# Buck.net
KiCad netlist of a schematic drawn in Altium Designer
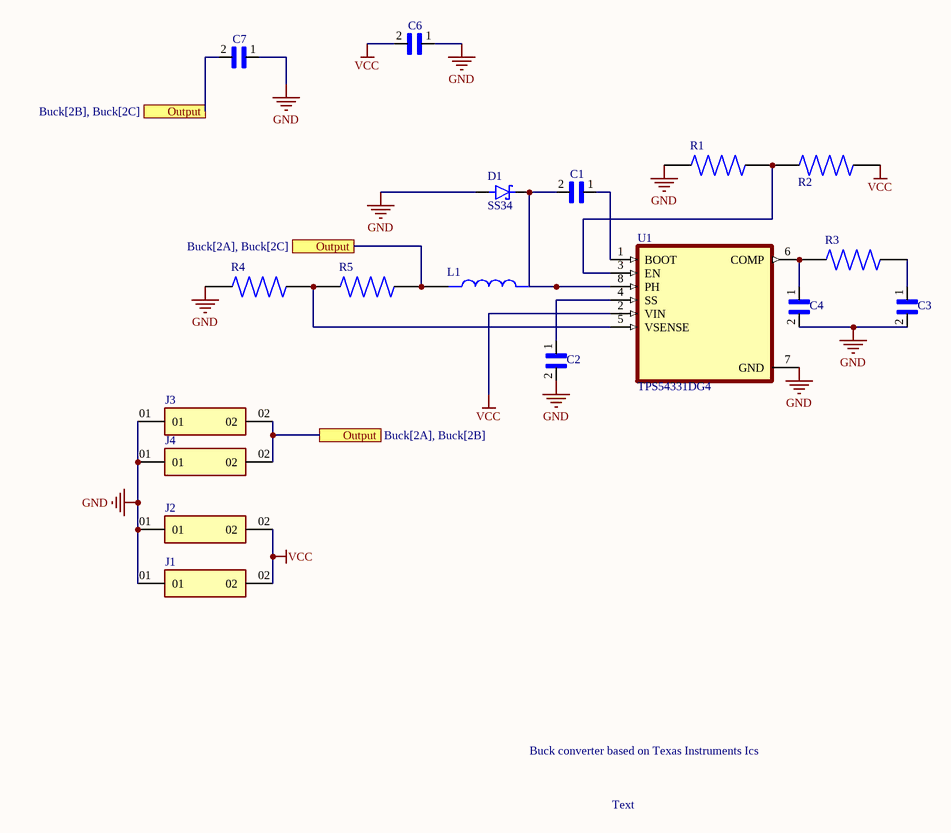
[diagram p0: Buck.SchDoc]

(export (version "E")
  (design (tool "Eeschema 10.0.6"))
  (components
    (comp (ref "C1")
      (value "~")
      (footprint "CAPC2012X135N")
      (description "SMD Capacitor X5R(EIA) with Capacitance: 22uF Tol. 20%. Rated Voltage: 25Vdc")
      (fields (field (name "MP") "GRM21BR61E226ME44K") (field (name "MF") "Murata Electronics"))
      (libsource (lib "GRM21BR61E226ME44K") (part "GRM21BR61E226ME44K"))
    )
    (comp (ref "C2")
      (value "~")
      (footprint "CAPC2012X135N")
      (description "SMD Capacitor X5R(EIA) with Capacitance: 22uF Tol. 20%. Rated Voltage: 25Vdc")
      (fields (field (name "MP") "GRM21BR61E226ME44K") (field (name "MF") "Murata Electronics"))
      (libsource (lib "") (part "GRM21BR61E226ME44K_1"))
    )
    (comp (ref "C3")
      (value "~")
      (footprint "CAPC2012X135N")
      (description "SMD Capacitor X5R(EIA) with Capacitance: 22uF Tol. 20%. Rated Voltage: 25Vdc")
      (fields (field (name "MP") "GRM21BR61E226ME44K") (field (name "MF") "Murata Electronics"))
      (libsource (lib "") (part "GRM21BR61E226ME44K_1"))
    )
    (comp (ref "C4")
      (value "~")
      (footprint "CAPC2012X135N")
      (description "SMD Capacitor X5R(EIA) with Capacitance: 22uF Tol. 20%. Rated Voltage: 25Vdc")
      (fields (field (name "MP") "GRM21BR61E226ME44K") (field (name "MF") "Murata Electronics"))
      (libsource (lib "") (part "GRM21BR61E226ME44K_1"))
    )
    (comp (ref "C6")
      (value "~")
      (footprint "CAPC2012X135N")
      (description "SMD Capacitor X5R(EIA) with Capacitance: 22uF Tol. 20%. Rated Voltage: 25Vdc")
      (fields (field (name "MP") "GRM21BR61E226ME44K") (field (name "MF") "Murata Electronics"))
      (libsource (lib "GRM21BR61E226ME44K") (part "GRM21BR61E226ME44K"))
    )
    (comp (ref "C7")
      (value "~")
      (footprint "CAPC2012X135N")
      (description "SMD Capacitor X5R(EIA) with Capacitance: 22uF Tol. 20%. Rated Voltage: 25Vdc")
      (fields (field (name "MP") "GRM21BR61E226ME44K") (field (name "MF") "Murata Electronics"))
      (libsource (lib "GRM21BR61E226ME44K") (part "GRM21BR61E226ME44K"))
    )
    (comp (ref "D1")
      (value "SS34")
      (footprint "DIO_SS34")
      (description "3A, 40V, Schottky Rectifier")
      (fields (field (name "MF") "Taiwan Semiconductor"))
      (libsource (lib "SS34") (part "SS34"))
    )
    (comp (ref "J1")
      (value "TSW-101-23-S-D-LL")
      (footprint "SAMTEC_TSW-101-23-S-D-LL")
      (libsource (lib "TSW-101-23-S-D-LL") (part "TSW-101-23-S-D-LL"))
    )
    (comp (ref "J2")
      (value "TSW-101-23-S-D-LL")
      (footprint "SAMTEC_TSW-101-23-S-D-LL")
      (libsource (lib "TSW-101-23-S-D-LL") (part "TSW-101-23-S-D-LL"))
    )
    (comp (ref "J3")
      (value "TSW-101-23-S-D-LL")
      (footprint "SAMTEC_TSW-101-23-S-D-LL")
      (libsource (lib "TSW-101-23-S-D-LL") (part "TSW-101-23-S-D-LL"))
    )
    (comp (ref "J4")
      (value "TSW-101-23-S-D-LL")
      (footprint "SAMTEC_TSW-101-23-S-D-LL")
      (libsource (lib "TSW-101-23-S-D-LL") (part "TSW-101-23-S-D-LL"))
    )
    (comp (ref "L1")
      (value "1255AY-100M=P3")
      (footprint "IND_1255AY-100M=P3")
      (description "Inductor with Inductance: 10uH Tol. +/-20%, Package: 2424 _6060_")
      (fields (field (name "MF") "Murata") (field (name "DIGI-KEY_PART_NUMBER") "490-10800-1-ND"))
      (libsource (lib "1255AY-100M_P3") (part "1255AY-100M=P3"))
    )
    (comp (ref "R1")
      (value "ERJU08J274V")
      (footprint "RES_ERJU08J274V")
      (description "1206 anti-sulfurated resistor 1206 Anti-Sulfurated")
      (fields (field (name "MF") "Panasonic") (field (name "MP") "ERJ-U08J274V"))
      (libsource (lib "ERJU08J274V") (part "ERJU08J274V"))
    )
    (comp (ref "R2")
      (value "ERJU08J274V")
      (footprint "RES_ERJU08J274V")
      (description "1206 anti-sulfurated resistor 1206 Anti-Sulfurated")
      (fields (field (name "MF") "Panasonic") (field (name "MP") "ERJ-U08J274V"))
      (libsource (lib "ERJU08J274V") (part "ERJU08J274V"))
    )
    (comp (ref "R3")
      (value "ERJU08J274V")
      (footprint "RES_ERJU08J274V")
      (description "1206 anti-sulfurated resistor 1206 Anti-Sulfurated")
      (fields (field (name "MF") "Panasonic") (field (name "MP") "ERJ-U08J274V"))
      (libsource (lib "ERJU08J274V") (part "ERJU08J274V"))
    )
    (comp (ref "R4")
      (value "ERJU08J274V")
      (footprint "RES_ERJU08J274V")
      (description "1206 anti-sulfurated resistor 1206 Anti-Sulfurated")
      (fields (field (name "MF") "Panasonic") (field (name "MP") "ERJ-U08J274V"))
      (libsource (lib "ERJU08J274V") (part "ERJU08J274V"))
    )
    (comp (ref "R5")
      (value "ERJU08J274V")
      (footprint "RES_ERJU08J274V")
      (description "1206 anti-sulfurated resistor 1206 Anti-Sulfurated")
      (fields (field (name "MF") "Panasonic") (field (name "MP") "ERJ-U08J274V"))
      (libsource (lib "ERJU08J274V") (part "ERJU08J274V"))
    )
    (comp (ref "U1")
      (value "TPS54331DG4")
      (footprint "SOIC127P599X175-8N")
      (description "3.5V to 28V Input, 3A, 570kHz Step-Down Converter with Eco-mode 8-SOIC -40 to 150")
      (fields (field (name "MF") "Texas Instruments"))
      (libsource (lib "TPS54331DG4") (part "TPS54331DG4"))
    )
  )
  (nets
    (net (code "1") (name "/Output") (class "Default")
      (node (ref "C7") (pin "2") (pinfunction "2_2") (pintype "passive"))
      (node (ref "J3") (pin "02") (pinfunction "02_02") (pintype "passive"))
      (node (ref "J4") (pin "02") (pinfunction "02_02") (pintype "passive"))
      (node (ref "L1") (pin "1") (pinfunction "1_1") (pintype "passive"))
      (node (ref "R5") (pin "2") (pinfunction "2_2") (pintype "passive"))
    )
    (net (code "2") (name "GND") (class "Default")
      (node (ref "C2") (pin "2") (pinfunction "2_2") (pintype "passive"))
      (node (ref "C3") (pin "2") (pinfunction "2_2") (pintype "passive"))
      (node (ref "C4") (pin "2") (pinfunction "2_2") (pintype "passive"))
      (node (ref "C6") (pin "1") (pinfunction "1_1") (pintype "passive"))
      (node (ref "C7") (pin "1") (pinfunction "1_1") (pintype "passive"))
      (node (ref "D1") (pin "A") (pinfunction "A_A") (pintype "passive"))
      (node (ref "J1") (pin "01") (pinfunction "01_01") (pintype "passive"))
      (node (ref "J2") (pin "01") (pinfunction "01_01") (pintype "passive"))
      (node (ref "J3") (pin "01") (pinfunction "01_01") (pintype "passive"))
      (node (ref "J4") (pin "01") (pinfunction "01_01") (pintype "passive"))
      (node (ref "R1") (pin "1") (pinfunction "1_1") (pintype "passive"))
      (node (ref "R4") (pin "1") (pinfunction "1_1") (pintype "passive"))
      (node (ref "U1") (pin "7") (pinfunction "GND_7") (pintype "power_in"))
    )
    (net (code "3") (name "Net-(C3-Pad1)") (class "Default")
      (node (ref "C3") (pin "1") (pinfunction "1_1") (pintype "passive"))
      (node (ref "R3") (pin "2") (pinfunction "2_2") (pintype "passive"))
    )
    (net (code "4") (name "Net-(D1-K)") (class "Default")
      (node (ref "C1") (pin "2") (pinfunction "2_2") (pintype "passive"))
      (node (ref "D1") (pin "C") (pinfunction "K_C") (pintype "passive"))
      (node (ref "L1") (pin "2") (pinfunction "2_2") (pintype "passive"))
      (node (ref "U1") (pin "8") (pinfunction "PH_8") (pintype "input"))
    )
    (net (code "5") (name "Net-(U1-BOOT)") (class "Default")
      (node (ref "C1") (pin "1") (pinfunction "1_1") (pintype "passive"))
      (node (ref "U1") (pin "1") (pinfunction "BOOT_1") (pintype "input"))
    )
    (net (code "6") (name "Net-(U1-COMP)") (class "Default")
      (node (ref "C4") (pin "1") (pinfunction "1_1") (pintype "passive"))
      (node (ref "R3") (pin "1") (pinfunction "1_1") (pintype "passive"))
      (node (ref "U1") (pin "6") (pinfunction "COMP_6") (pintype "output"))
    )
    (net (code "7") (name "Net-(U1-EN)") (class "Default")
      (node (ref "R1") (pin "2") (pinfunction "2_2") (pintype "passive"))
      (node (ref "R2") (pin "2") (pinfunction "2_2") (pintype "passive"))
      (node (ref "U1") (pin "3") (pinfunction "EN_3") (pintype "input"))
    )
    (net (code "8") (name "Net-(U1-SS)") (class "Default")
      (node (ref "C2") (pin "1") (pinfunction "1_1") (pintype "passive"))
      (node (ref "U1") (pin "4") (pinfunction "SS_4") (pintype "input"))
    )
    (net (code "9") (name "Net-(U1-VSENSE)") (class "Default")
      (node (ref "R4") (pin "2") (pinfunction "2_2") (pintype "passive"))
      (node (ref "R5") (pin "1") (pinfunction "1_1") (pintype "passive"))
      (node (ref "U1") (pin "5") (pinfunction "VSENSE_5") (pintype "input"))
    )
    (net (code "10") (name "VCC") (class "Default")
      (node (ref "C6") (pin "2") (pinfunction "2_2") (pintype "passive"))
      (node (ref "J1") (pin "02") (pinfunction "02_02") (pintype "passive"))
      (node (ref "J2") (pin "02") (pinfunction "02_02") (pintype "passive"))
      (node (ref "R2") (pin "1") (pinfunction "1_1") (pintype "passive"))
      (node (ref "U1") (pin "2") (pinfunction "VIN_2") (pintype "input"))
    )
  )
)
